# 04_Mechanical.net
KiCad netlist of a schematic drawn in Altium Designer
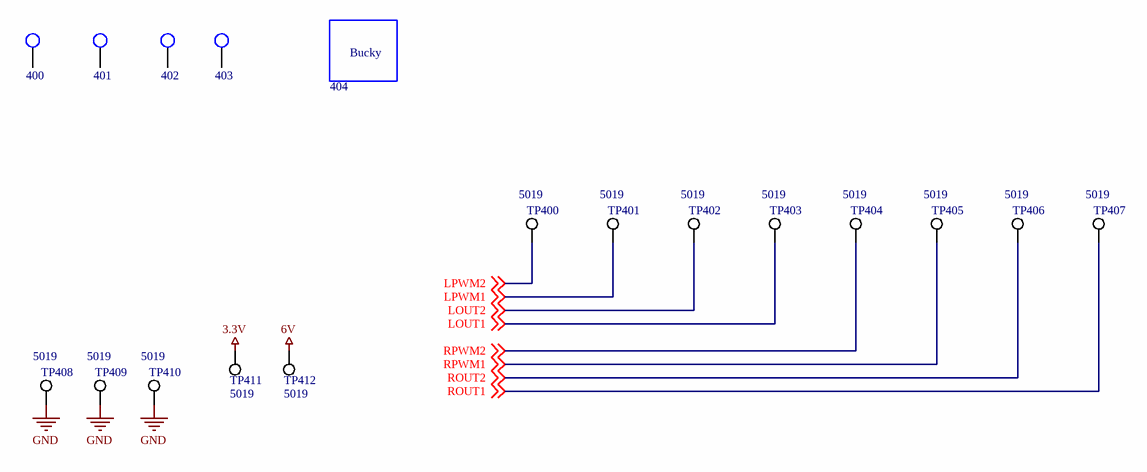
[diagram p0: 04_Mechanical.SchDoc]

(export (version "E")
  (design (tool "Eeschema 10.0.6"))
  (components
    (comp (ref "400")
      (value "MHOLE_2_55MM")
      (footprint "MHOLE_2_55MM")
      (description "Mounting Holde")
      (fields (field (name "MANUFACTURER PART NUMBER") "UW MTHOLE"))
      (libsource (lib "ECE453_S24") (part "MHOLE_2_55MM"))
    )
    (comp (ref "401")
      (value "MHOLE_2_55MM")
      (footprint "MHOLE_2_55MM")
      (description "Mounting Holde")
      (fields (field (name "MANUFACTURER PART NUMBER") "UW MTHOLE"))
      (libsource (lib "ECE453_S24") (part "MHOLE_2_55MM"))
    )
    (comp (ref "402")
      (value "MHOLE_2_55MM")
      (footprint "MHOLE_2_55MM")
      (description "Mounting Holde")
      (fields (field (name "MANUFACTURER PART NUMBER") "UW MTHOLE"))
      (libsource (lib "ECE453_S24") (part "MHOLE_2_55MM"))
    )
    (comp (ref "403")
      (value "MHOLE_2_55MM")
      (footprint "MHOLE_2_55MM")
      (description "Mounting Holde")
      (fields (field (name "MANUFACTURER PART NUMBER") "UW MTHOLE"))
      (libsource (lib "ECE453_S24") (part "MHOLE_2_55MM"))
    )
    (comp (ref "404")
      (value "Bucky")
      (footprint "WalkingBucky")
      (description "Bucky Badger Image")
      (fields (field (name "MANUFACTURER PART NUMBER") "UW Bucky"))
      (libsource (lib "ECE453") (part "Bucky"))
    )
    (comp (ref "TP400")
      (value "5019")
      (footprint "KSTN-5019_V")
      (description "Test Point, 1 Position SMD, RoHS, Tape and Reel")
      (libsource (lib "Altium Content Vault") (part "TESTPOINT_WHITE"))
    )
    (comp (ref "TP401")
      (value "5019")
      (footprint "KSTN-5019_V")
      (description "Test Point, 1 Position SMD, RoHS, Tape and Reel")
      (libsource (lib "Altium Content Vault") (part "TESTPOINT_WHITE"))
    )
    (comp (ref "TP402")
      (value "5019")
      (footprint "KSTN-5019_V")
      (description "Test Point, 1 Position SMD, RoHS, Tape and Reel")
      (libsource (lib "Altium Content Vault") (part "TESTPOINT_WHITE"))
    )
    (comp (ref "TP403")
      (value "5019")
      (footprint "KSTN-5019_V")
      (description "Test Point, 1 Position SMD, RoHS, Tape and Reel")
      (libsource (lib "Altium Content Vault") (part "TESTPOINT_WHITE"))
    )
    (comp (ref "TP404")
      (value "5019")
      (footprint "KSTN-5019_V")
      (description "Test Point, 1 Position SMD, RoHS, Tape and Reel")
      (libsource (lib "Altium Content Vault") (part "TESTPOINT_WHITE"))
    )
    (comp (ref "TP405")
      (value "5019")
      (footprint "KSTN-5019_V")
      (description "Test Point, 1 Position SMD, RoHS, Tape and Reel")
      (libsource (lib "Altium Content Vault") (part "TESTPOINT_WHITE"))
    )
    (comp (ref "TP406")
      (value "5019")
      (footprint "KSTN-5019_V")
      (description "Test Point, 1 Position SMD, RoHS, Tape and Reel")
      (libsource (lib "Altium Content Vault") (part "TESTPOINT_WHITE"))
    )
    (comp (ref "TP407")
      (value "5019")
      (footprint "KSTN-5019_V")
      (description "Test Point, 1 Position SMD, RoHS, Tape and Reel")
      (libsource (lib "Altium Content Vault") (part "TESTPOINT_WHITE"))
    )
    (comp (ref "TP408")
      (value "5019")
      (footprint "KSTN-5019_V")
      (description "Test Point, 1 Position SMD, RoHS, Tape and Reel")
      (libsource (lib "Altium Content Vault") (part "TESTPOINT_WHITE"))
    )
    (comp (ref "TP409")
      (value "5019")
      (footprint "KSTN-5019_V")
      (description "Test Point, 1 Position SMD, RoHS, Tape and Reel")
      (libsource (lib "Altium Content Vault") (part "TESTPOINT_WHITE"))
    )
    (comp (ref "TP410")
      (value "5019")
      (footprint "KSTN-5019_V")
      (description "Test Point, 1 Position SMD, RoHS, Tape and Reel")
      (libsource (lib "Altium Content Vault") (part "TESTPOINT_WHITE"))
    )
    (comp (ref "TP411")
      (value "5019")
      (footprint "KSTN-5019_V")
      (description "Test Point, 1 Position SMD, RoHS, Tape and Reel")
      (libsource (lib "Altium Content Vault") (part "TESTPOINT_WHITE"))
    )
    (comp (ref "TP412")
      (value "5019")
      (footprint "KSTN-5019_V")
      (description "Test Point, 1 Position SMD, RoHS, Tape and Reel")
      (libsource (lib "Altium Content Vault") (part "TESTPOINT_WHITE"))
    )
  )
  (nets
    (net (code "1") (name "3.3V") (class "Default")
      (node (ref "TP411") (pin "1") (pinfunction "1_1") (pintype "passive"))
    )
    (net (code "2") (name "6V") (class "Default")
      (node (ref "TP412") (pin "1") (pinfunction "1_1") (pintype "passive"))
    )
    (net (code "3") (name "GND") (class "Default")
      (node (ref "TP408") (pin "1") (pinfunction "1_1") (pintype "passive"))
      (node (ref "TP409") (pin "1") (pinfunction "1_1") (pintype "passive"))
      (node (ref "TP410") (pin "1") (pinfunction "1_1") (pintype "passive"))
    )
    (net (code "4") (name "LOUT1") (class "Default")
      (node (ref "TP403") (pin "1") (pinfunction "1_1") (pintype "passive"))
    )
    (net (code "5") (name "LOUT2") (class "Default")
      (node (ref "TP402") (pin "1") (pinfunction "1_1") (pintype "passive"))
    )
    (net (code "6") (name "LPWM1") (class "Default")
      (node (ref "TP401") (pin "1") (pinfunction "1_1") (pintype "passive"))
    )
    (net (code "7") (name "LPWM2") (class "Default")
      (node (ref "TP400") (pin "1") (pinfunction "1_1") (pintype "passive"))
    )
    (net (code "8") (name "ROUT1") (class "Default")
      (node (ref "TP407") (pin "1") (pinfunction "1_1") (pintype "passive"))
    )
    (net (code "9") (name "ROUT2") (class "Default")
      (node (ref "TP406") (pin "1") (pinfunction "1_1") (pintype "passive"))
    )
    (net (code "10") (name "RPWM1") (class "Default")
      (node (ref "TP405") (pin "1") (pinfunction "1_1") (pintype "passive"))
    )
    (net (code "11") (name "RPWM2") (class "Default")
      (node (ref "TP404") (pin "1") (pinfunction "1_1") (pintype "passive"))
    )
    (net (code "12") (name "unconnected-(400-Pad1)") (class "Default")
      (node (ref "400") (pin "1") (pintype "passive"))
    )
    (net (code "13") (name "unconnected-(401-Pad1)") (class "Default")
      (node (ref "401") (pin "1") (pintype "passive"))
    )
    (net (code "14") (name "unconnected-(402-Pad1)") (class "Default")
      (node (ref "402") (pin "1") (pintype "passive"))
    )
    (net (code "15") (name "unconnected-(403-Pad1)") (class "Default")
      (node (ref "403") (pin "1") (pintype "passive"))
    )
  )
)
